# RP_ComputeModule3_rev_3_0_BootSelector.net
KiCad netlist of a schematic drawn in Altium Designer
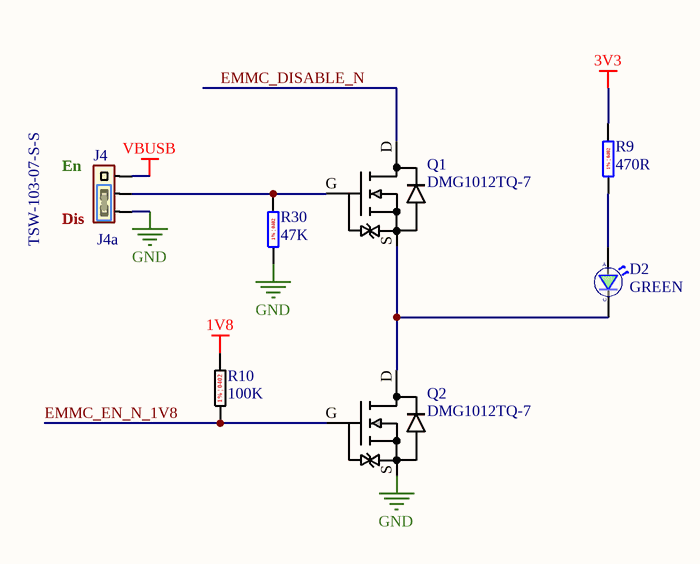
[diagram p0: RP_ComputeModule3_rev.3.0_BootSelector.SchDoc]

(export (version "E")
  (design (tool "Eeschema 10.0.6"))
  (components
    (comp (ref "D2")
      (value "GREEN")
      (footprint "ROHM 0603 LED")
      (description "LED GREEN DIFFUSED 0603 SMD")
      (fields (field (name "MANUFACTURER") "Rohm") (field (name "MANUFACTURER PART NUMBER") "SML-D12M8WT86"))
      (libsource (lib "Rohm_Library") (part "SML-D12M8WT86"))
    )
    (comp (ref "J4")
      (value "TSW-103-07-S-S")
      (footprint "Samtec TSW-103-07-S-S")
      (description "Conn Unshrouded Header HDR 3 POS 2.54mm Solder ST Thru-Hole Bulk")
      (fields (field (name "MANUFACTURER") "Samtec"))
      (libsource (lib "Samtec_Library") (part "TSW-103-07-S-S"))
    )
    (comp (ref "J4a")
      (value "Jumper")
      (footprint "Kobiconn 151-8011-E (Blue)")
      (description "Headers & Wire Housings MINI JUMPER GF 6.0MM CLOSE TYPE BLUE")
      (fields (field (name "MANUFACTURER") "Kobiconn") (field (name "MANUFACTURER PART NUMBER") "151-8011-E"))
      (libsource (lib "Kobiconn_Library") (part "151-8011-E"))
    )
    (comp (ref "Q1")
      (value "DMG1012TQ-7")
      (footprint "Diodes SOT523")
      (description "MOSFET NCH 20V 630MA SOT523")
      (fields (field (name "MANUFACTURER") "Diodes"))
      (libsource (lib "Diodes_Inc_Library") (part "DMG1012TQ-7"))
    )
    (comp (ref "Q2")
      (value "DMG1012TQ-7")
      (footprint "Diodes SOT523")
      (description "MOSFET NCH 20V 630MA SOT523")
      (fields (field (name "MANUFACTURER") "Diodes"))
      (libsource (lib "Diodes_Inc_Library") (part "DMG1012TQ-7"))
    )
    (comp (ref "R9")
      (value "470R")
      (footprint "Vishay RES0402")
      (description "RES SMD 470 OHM 1% 1/10W 0402")
      (fields
        (field (name "MANUFACTURER") "Vishay BCcomponents")
        (field (name "MANUFACTURER PART NUMBER") "MCS04020C4700FE000")
      )
      (libsource (lib "Vishay_Library") (part "MCS04020C4700FE000"))
    )
    (comp (ref "R10")
      (value "100K")
      (footprint "RES0402")
      (description "Thick Film Resistors - SMD 0.125W 100Kohm 1% 200ppm")
      (fields
        (field (name "MANUFACTURER") "KOA Speer")
        (field (name "MANUFACTURER PART NUMBER") "SG73P1ETTP1003F")
      )
      (libsource (lib "KOA_Resistors") (part "SG73P1ETTP1003F"))
    )
    (comp (ref "R30")
      (value "47K")
      (footprint "Vishay Beyschlag MCS0402")
      (description "Res Thin Film 0402 47K Ohm 1% 1/16W ±50ppm/C Molded SMD Paper T/R")
      (fields
        (field (name "MANUFACTURER") "Vishay BCcomponents")
        (field (name "MANUFACTURER PART NUMBER") "MCS04020C4702FE000")
      )
      (libsource (lib "Vishay_Library") (part "MCS04020C4702FE000"))
    )
  )
  (nets
    (net (code "1") (name "/EMMC_DISABLE_N") (class "Default")
      (node (ref "Q1") (pin "D") (pinfunction "D_D") (pintype "passive"))
    )
    (net (code "2") (name "/EMMC_EN_N_1V8") (class "Default")
      (node (ref "Q2") (pin "G") (pinfunction "G_G") (pintype "passive"))
      (node (ref "R10") (pin "2") (pinfunction "2_2") (pintype "passive"))
    )
    (net (code "3") (name "1V8") (class "Default")
      (node (ref "R10") (pin "1") (pinfunction "1_1") (pintype "passive"))
    )
    (net (code "4") (name "3V3") (class "Default")
      (node (ref "R9") (pin "1") (pinfunction "1_1") (pintype "passive"))
    )
    (net (code "5") (name "GND") (class "Default")
      (node (ref "J4") (pin "1") (pinfunction "1_1") (pintype "passive"))
      (node (ref "Q2") (pin "S") (pinfunction "S_S") (pintype "passive"))
      (node (ref "R30") (pin "2") (pinfunction "2_2") (pintype "passive"))
    )
    (net (code "6") (name "Net-(D2-PadA)") (class "Default")
      (node (ref "D2") (pin "A") (pinfunction "A_A") (pintype "passive"))
      (node (ref "R9") (pin "2") (pinfunction "2_2") (pintype "passive"))
    )
    (net (code "7") (name "Net-(D2-PadC)") (class "Default")
      (node (ref "D2") (pin "C") (pinfunction "C_C") (pintype "passive"))
      (node (ref "Q1") (pin "S") (pinfunction "S_S") (pintype "passive"))
      (node (ref "Q2") (pin "D") (pinfunction "D_D") (pintype "passive"))
    )
    (net (code "8") (name "Net-(J4-Pad2)") (class "Default")
      (node (ref "J4") (pin "2") (pinfunction "2_2") (pintype "passive"))
      (node (ref "Q1") (pin "G") (pinfunction "G_G") (pintype "passive"))
      (node (ref "R30") (pin "1") (pinfunction "1_1") (pintype "passive"))
    )
    (net (code "9") (name "VBUSB") (class "Default")
      (node (ref "J4") (pin "3") (pinfunction "3_3") (pintype "passive"))
    )
  )
)
